# ADIS_Teensy_Arduino_Breakout_RevA.net
KiCad netlist of a schematic drawn in EAGLE
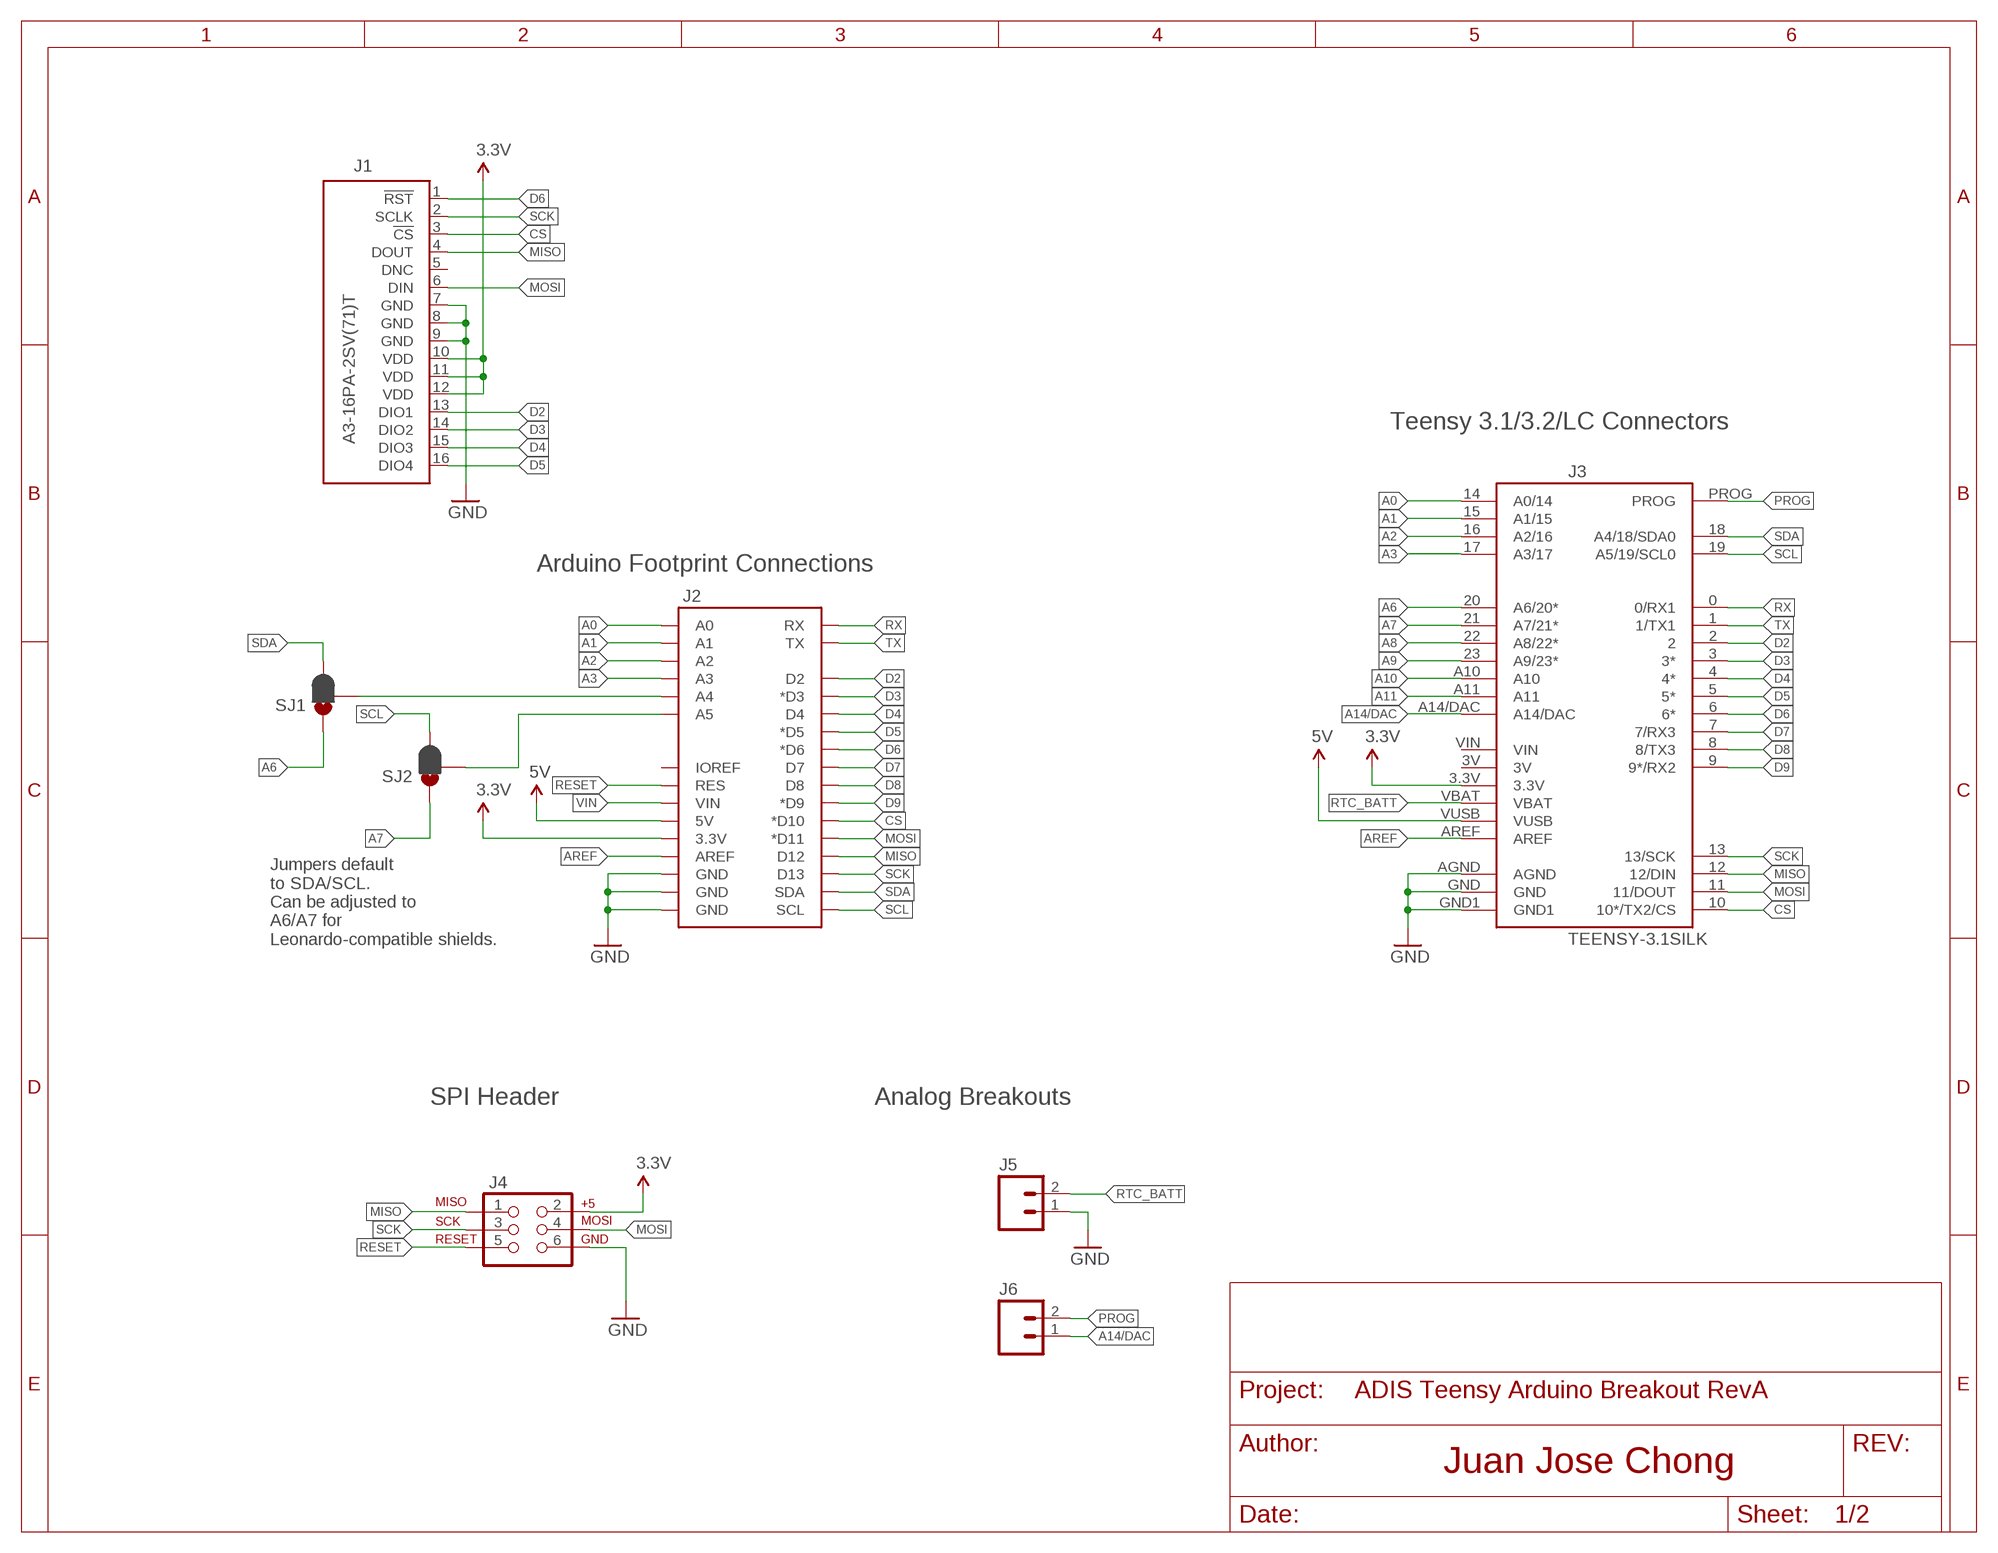
[diagram p0: schematic, sheet 1]
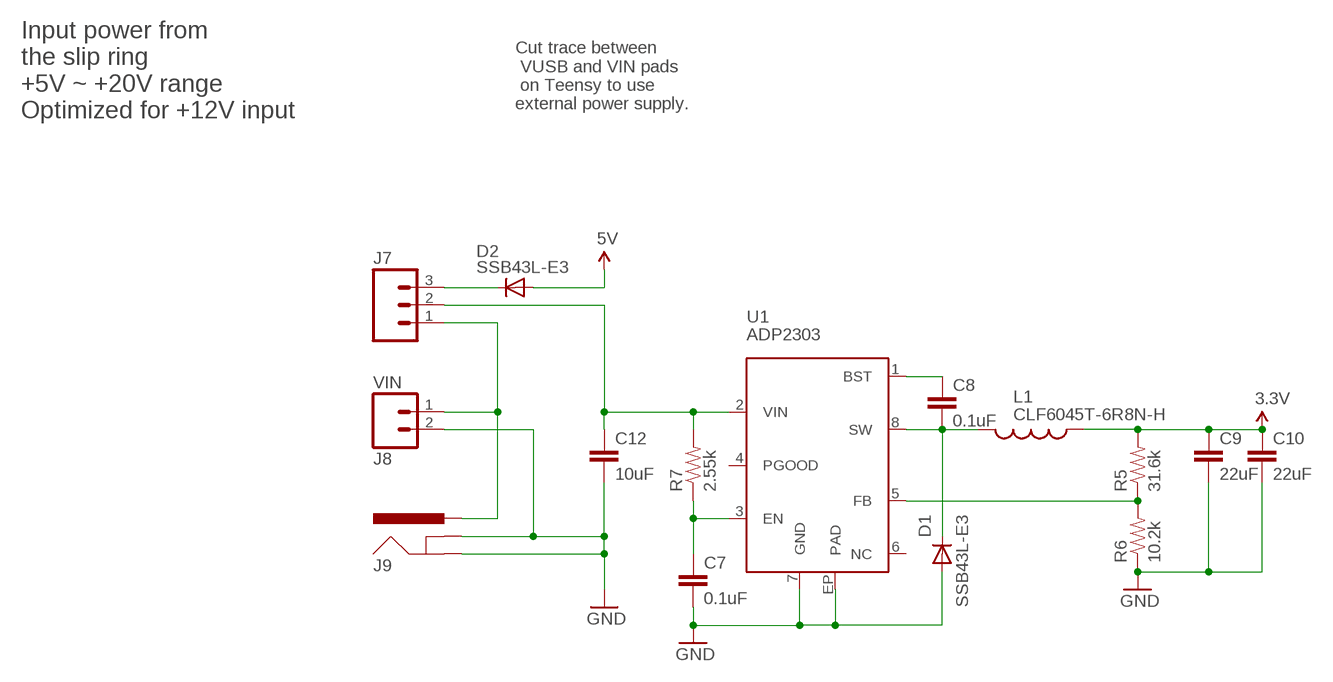
[diagram p1: schematic, sheet 2]

(export (version "E")
  (design (tool "Eeschema 10.0.6"))
  (components
    (comp (ref "C7")
      (value "0.1uF")
      (footprint "eagle-import:0603-CAP")
      (fields (field (name "PARTNO") "CL10B104KB8NNNC"))
      (libsource (lib "eagle-import") (part "CAP0603-CAP"))
    )
    (comp (ref "C8")
      (value "0.1uF")
      (footprint "eagle-import:0603-CAP")
      (fields (field (name "PARTNO") "CL10B104KB8NNNC"))
      (libsource (lib "eagle-import") (part "CAP0603-CAP"))
    )
    (comp (ref "C9")
      (value "22uF")
      (footprint "eagle-import:1210")
      (fields (field (name "PARTNO") "TLJA476M010R0600"))
      (libsource (lib "eagle-import") (part "CAP1210"))
    )
    (comp (ref "C10")
      (value "22uF")
      (footprint "eagle-import:1210")
      (fields (field (name "PARTNO") "TLJA476M010R0600"))
      (libsource (lib "eagle-import") (part "CAP1210"))
    )
    (comp (ref "C12")
      (value "10uF")
      (footprint "eagle-import:1206")
      (fields (field (name "PARTNO") "TLJA476M010R0600"))
      (libsource (lib "eagle-import") (part "CAP1206"))
    )
    (comp (ref "D1")
      (value "SSB43L-E3")
      (footprint "eagle-import:DO214AA")
      (fields (field (name "PARTNO") "SSB43L-E3/52T"))
      (libsource (lib "eagle-import") (part "DIODE-DO214AA"))
    )
    (comp (ref "D2")
      (value "SSB43L-E3")
      (footprint "eagle-import:DO214AA")
      (fields (field (name "PARTNO") "SSB43L-E3/52T"))
      (libsource (lib "eagle-import") (part "DIODE-DO214AA"))
    )
    (comp (ref "J7")
      (value "M03PTH")
      (footprint "eagle-import:1X03")
      (libsource (lib "eagle-import") (part "M03PTH"))
    )
    (comp (ref "J8")
      (value "VIN")
      (footprint "eagle-import:SCREWTERMINAL-3.5MM-2")
      (fields (field (name "PARTNO") "20020327-C021B01LF"))
      (libsource (lib "eagle-import") (part "M023.5MM"))
    )
    (comp (ref "J9")
      (value "POWER_JACKPTH_LOCK")
      (footprint "eagle-import:POWER_JACK_PTH_LOCK")
      (libsource (lib "eagle-import") (part "POWER_JACKPTH_LOCK"))
    )
    (comp (ref "L1")
      (value "CLF6045T-6R8N-H")
      (footprint "eagle-import:CLF6045-H")
      (libsource (lib "eagle-import") (part "CLF6045T-6R8N-H"))
    )
    (comp (ref "R5")
      (value "31.6k")
      (footprint "eagle-import:0603-RES")
      (fields (field (name "PARTNO") "ERJ-3EKF3162V"))
      (libsource (lib "eagle-import") (part "RESISTOR0603-RES"))
    )
    (comp (ref "R6")
      (value "10.2k")
      (footprint "eagle-import:0603-RES")
      (fields (field (name "PARTNO") "ERJ-3EKF1022V"))
      (libsource (lib "eagle-import") (part "RESISTOR0603-RES"))
    )
    (comp (ref "R7")
      (value "2.55k")
      (footprint "eagle-import:0603-RES")
      (fields (field (name "PARTNO") "ERJ-3EKF2551V"))
      (libsource (lib "eagle-import") (part "RESISTOR0603-RES"))
    )
    (comp (ref "U1")
      (value "ADP2303")
      (footprint "eagle-import:SOIC-8-PAD")
      (fields (field (name "PARTNO") "ADP2303ARDZ"))
      (libsource (lib "eagle-import") (part "ADP2303"))
    )
    (comp (ref "J1")
      (value "A3-16PA-2SV(71)T")
      (footprint "eagle-import:A3-16PA-2SV(71)-TOP")
      (libsource (lib "eagle-import") (part "A3-16PA-2SV(71)T"))
    )
    (comp (ref "J2")
      (value "ARDUINO_R3_SHIELDUNO_R3_SHIELD_HOLES")
      (footprint "eagle-import:UNO_R3_SHIELD_HOLES")
      (libsource (lib "eagle-import") (part "ARDUINO_R3_SHIELDUNO_R3_SHIELD_HOLES"))
    )
    (comp (ref "J3")
      (value "TEENSY-3.1SILK")
      (footprint "eagle-import:TEENSY-3.1")
      (libsource (lib "eagle-import") (part "TEENSY-3.1SILK"))
    )
    (comp (ref "J4")
      (value "AVR_SPI_PRG_6PTH")
      (footprint "eagle-import:2X3")
      (libsource (lib "eagle-import") (part "AVR_SPI_PRG_6PTH"))
    )
    (comp (ref "J5")
      (value "M02PTH")
      (footprint "eagle-import:1X02")
      (libsource (lib "eagle-import") (part "M02PTH"))
    )
    (comp (ref "J6")
      (value "M02PTH")
      (footprint "eagle-import:1X02")
      (libsource (lib "eagle-import") (part "M02PTH"))
    )
    (comp (ref "SJ1")
      (value "JUMPER-PAD-3-2OF3_NC_BY_PASTE")
      (footprint "eagle-import:PAD-JUMPER-3-2OF3_NC_BY_PASTE_YES_SILK_FULL_BOX")
      (libsource (lib "eagle-import") (part "JUMPER-PAD-3-2OF3_NC_BY_PASTE"))
    )
    (comp (ref "SJ2")
      (value "JUMPER-PAD-3-2OF3_NC_BY_PASTE")
      (footprint "eagle-import:PAD-JUMPER-3-2OF3_NC_BY_PASTE_YES_SILK_FULL_BOX")
      (libsource (lib "eagle-import") (part "JUMPER-PAD-3-2OF3_NC_BY_PASTE"))
    )
  )
  (nets
    (net (code "1") (name "3.3V") (class "Default")
      (node (ref "C10") (pin "1") (pinfunction "1_1") (pintype "passive"))
      (node (ref "C9") (pin "1") (pinfunction "1_1") (pintype "passive"))
      (node (ref "J1") (pin "10") (pinfunction "VDD_10") (pintype "bidirectional"))
      (node (ref "J1") (pin "11") (pinfunction "VDD_11") (pintype "bidirectional"))
      (node (ref "J1") (pin "12") (pinfunction "VDD_12") (pintype "bidirectional"))
      (node (ref "J2") (pin "3.3V") (pinfunction "3.3V_3.3V") (pintype "bidirectional"))
      (node (ref "J3") (pin "3.3V") (pinfunction "3.3V_3.3V") (pintype "bidirectional"))
      (node (ref "J4") (pin "2") (pinfunction "2_2") (pintype "passive"))
      (node (ref "L1") (pin "P$1") (pinfunction "1_P$1") (pintype "passive"))
      (node (ref "R5") (pin "2") (pinfunction "2_2") (pintype "passive"))
    )
    (net (code "2") (name "5V") (class "Default")
      (node (ref "D2") (pin "A") (pinfunction "A_A") (pintype "passive"))
      (node (ref "J2") (pin "5V") (pinfunction "5V_5V") (pintype "bidirectional"))
      (node (ref "J3") (pin "VUSB") (pinfunction "VUSB_VUSB") (pintype "bidirectional"))
    )
    (net (code "3") (name "A0") (class "Default")
      (node (ref "J2") (pin "A0") (pinfunction "A0_A0") (pintype "bidirectional"))
      (node (ref "J3") (pin "14") (pinfunction "A0/14_14") (pintype "bidirectional"))
    )
    (net (code "4") (name "A1") (class "Default")
      (node (ref "J2") (pin "A1") (pinfunction "A1_A1") (pintype "bidirectional"))
      (node (ref "J3") (pin "15") (pinfunction "A1/15_15") (pintype "bidirectional"))
    )
    (net (code "5") (name "A2") (class "Default")
      (node (ref "J2") (pin "A2") (pinfunction "A2_A2") (pintype "bidirectional"))
      (node (ref "J3") (pin "16") (pinfunction "A2/16_16") (pintype "bidirectional"))
    )
    (net (code "6") (name "A3") (class "Default")
      (node (ref "J2") (pin "A3") (pinfunction "A3_A3") (pintype "bidirectional"))
      (node (ref "J3") (pin "17") (pinfunction "A3/17_17") (pintype "bidirectional"))
    )
    (net (code "7") (name "A6") (class "Default")
      (node (ref "J3") (pin "20") (pinfunction "A6/20*_20") (pintype "bidirectional"))
      (node (ref "SJ1") (pin "1") (pinfunction "1_1") (pintype "passive"))
    )
    (net (code "8") (name "A7") (class "Default")
      (node (ref "J3") (pin "21") (pinfunction "A7/21*_21") (pintype "bidirectional"))
      (node (ref "SJ2") (pin "1") (pinfunction "1_1") (pintype "passive"))
    )
    (net (code "9") (name "A8") (class "Default")
      (node (ref "J3") (pin "22") (pinfunction "A8/22*_22") (pintype "bidirectional"))
    )
    (net (code "10") (name "A9") (class "Default")
      (node (ref "J3") (pin "23") (pinfunction "A9/23*_23") (pintype "bidirectional"))
    )
    (net (code "11") (name "A10") (class "Default")
      (node (ref "J3") (pin "A10") (pinfunction "A10_A10") (pintype "bidirectional"))
    )
    (net (code "12") (name "A11") (class "Default")
      (node (ref "J3") (pin "A11") (pinfunction "A11_A11") (pintype "bidirectional"))
    )
    (net (code "13") (name "A14{slash}DAC") (class "Default")
      (node (ref "J3") (pin "A14/DAC") (pinfunction "A14/DAC_A14/DAC") (pintype "bidirectional"))
      (node (ref "J6") (pin "1") (pinfunction "1_1") (pintype "passive"))
    )
    (net (code "14") (name "AREF") (class "Default")
      (node (ref "J2") (pin "AREF") (pinfunction "AREF_AREF") (pintype "bidirectional"))
      (node (ref "J3") (pin "AREF") (pinfunction "AREF_AREF") (pintype "bidirectional"))
    )
    (net (code "15") (name "CS") (class "Default")
      (node (ref "J1") (pin "3") (pinfunction "~{CS}_3") (pintype "bidirectional"))
      (node (ref "J2") (pin "D10") (pinfunction "*D10_D10") (pintype "bidirectional"))
      (node (ref "J3") (pin "10") (pinfunction "10*/TX2/CS_10") (pintype "bidirectional"))
    )
    (net (code "16") (name "D2") (class "Default")
      (node (ref "J1") (pin "13") (pinfunction "DIO1_13") (pintype "bidirectional"))
      (node (ref "J2") (pin "D2") (pinfunction "D2_D2") (pintype "bidirectional"))
      (node (ref "J3") (pin "2") (pinfunction "2_2") (pintype "bidirectional"))
    )
    (net (code "17") (name "D3") (class "Default")
      (node (ref "J1") (pin "14") (pinfunction "DIO2_14") (pintype "bidirectional"))
      (node (ref "J2") (pin "D3") (pinfunction "*D3_D3") (pintype "bidirectional"))
      (node (ref "J3") (pin "3") (pinfunction "3*_3") (pintype "bidirectional"))
    )
    (net (code "18") (name "D4") (class "Default")
      (node (ref "J1") (pin "15") (pinfunction "DIO3_15") (pintype "bidirectional"))
      (node (ref "J2") (pin "D4") (pinfunction "D4_D4") (pintype "bidirectional"))
      (node (ref "J3") (pin "4") (pinfunction "4*_4") (pintype "bidirectional"))
    )
    (net (code "19") (name "D5") (class "Default")
      (node (ref "J1") (pin "16") (pinfunction "DIO4_16") (pintype "bidirectional"))
      (node (ref "J2") (pin "D5") (pinfunction "*D5_D5") (pintype "bidirectional"))
      (node (ref "J3") (pin "5") (pinfunction "5*_5") (pintype "bidirectional"))
    )
    (net (code "20") (name "D6") (class "Default")
      (node (ref "J1") (pin "1") (pinfunction "~{RST}_1") (pintype "bidirectional"))
      (node (ref "J2") (pin "D6") (pinfunction "*D6_D6") (pintype "bidirectional"))
      (node (ref "J3") (pin "6") (pinfunction "6*_6") (pintype "bidirectional"))
    )
    (net (code "21") (name "D7") (class "Default")
      (node (ref "J2") (pin "D7") (pinfunction "D7_D7") (pintype "bidirectional"))
      (node (ref "J3") (pin "7") (pinfunction "7/RX3_7") (pintype "bidirectional"))
    )
    (net (code "22") (name "D8") (class "Default")
      (node (ref "J2") (pin "D8") (pinfunction "D8_D8") (pintype "bidirectional"))
      (node (ref "J3") (pin "8") (pinfunction "8/TX3_8") (pintype "bidirectional"))
    )
    (net (code "23") (name "D9") (class "Default")
      (node (ref "J2") (pin "D9") (pinfunction "*D9_D9") (pintype "bidirectional"))
      (node (ref "J3") (pin "9") (pinfunction "9*/RX2_9") (pintype "bidirectional"))
    )
    (net (code "24") (name "GND") (class "Default")
      (node (ref "C10") (pin "2") (pinfunction "2_2") (pintype "passive"))
      (node (ref "C12") (pin "2") (pinfunction "2_2") (pintype "passive"))
      (node (ref "C7") (pin "2") (pinfunction "2_2") (pintype "passive"))
      (node (ref "C9") (pin "2") (pinfunction "2_2") (pintype "passive"))
      (node (ref "D1") (pin "A") (pinfunction "A_A") (pintype "passive"))
      (node (ref "J1") (pin "7") (pinfunction "GND_7") (pintype "bidirectional"))
      (node (ref "J1") (pin "8") (pinfunction "GND_8") (pintype "bidirectional"))
      (node (ref "J1") (pin "9") (pinfunction "GND_9") (pintype "bidirectional"))
      (node (ref "J2") (pin "GND@0") (pinfunction "GND_GND@0") (pintype "bidirectional"))
      (node (ref "J2") (pin "GND@1") (pinfunction "GND_GND@1") (pintype "bidirectional"))
      (node (ref "J2") (pin "GND@2") (pinfunction "GND_GND@2") (pintype "bidirectional"))
      (node (ref "J3") (pin "AGND") (pinfunction "AGND_AGND") (pintype "bidirectional"))
      (node (ref "J3") (pin "GND") (pinfunction "GND_GND") (pintype "bidirectional"))
      (node (ref "J3") (pin "GND1") (pinfunction "GND1_GND1") (pintype "bidirectional"))
      (node (ref "J4") (pin "6") (pinfunction "6_6") (pintype "passive"))
      (node (ref "J5") (pin "1") (pinfunction "1_1") (pintype "passive"))
      (node (ref "J8") (pin "2") (pinfunction "2_2") (pintype "passive"))
      (node (ref "J9") (pin "GND") (pinfunction "GND_GND") (pintype "bidirectional"))
      (node (ref "J9") (pin "GNDBREAK") (pinfunction "GNDBREAK_GNDBREAK") (pintype "bidirectional"))
      (node (ref "R6") (pin "1") (pinfunction "1_1") (pintype "passive"))
      (node (ref "U1") (pin "7") (pinfunction "GND_7") (pintype "bidirectional"))
      (node (ref "U1") (pin "EP") (pinfunction "PAD_EP") (pintype "bidirectional"))
    )
    (net (code "25") (name "MISO") (class "Default")
      (node (ref "J1") (pin "4") (pinfunction "DOUT_4") (pintype "bidirectional"))
      (node (ref "J2") (pin "D12") (pinfunction "D12_D12") (pintype "bidirectional"))
      (node (ref "J3") (pin "12") (pinfunction "12/DIN_12") (pintype "bidirectional"))
      (node (ref "J4") (pin "1") (pinfunction "1_1") (pintype "passive"))
    )
    (net (code "26") (name "MOSI") (class "Default")
      (node (ref "J1") (pin "6") (pinfunction "DIN_6") (pintype "bidirectional"))
      (node (ref "J2") (pin "D11") (pinfunction "*D11_D11") (pintype "bidirectional"))
      (node (ref "J3") (pin "11") (pinfunction "11/DOUT_11") (pintype "bidirectional"))
      (node (ref "J4") (pin "4") (pinfunction "4_4") (pintype "passive"))
    )
    (net (code "27") (name "Net-(D2-PadC)") (class "Default")
      (node (ref "D2") (pin "C") (pinfunction "C_C") (pintype "passive"))
      (node (ref "J7") (pin "3") (pinfunction "3_3") (pintype "passive"))
    )
    (net (code "28") (name "Net-(J2-PadA4)") (class "Default")
      (node (ref "J2") (pin "A4") (pinfunction "A4_A4") (pintype "bidirectional"))
      (node (ref "SJ1") (pin "2") (pinfunction "2_2") (pintype "passive"))
    )
    (net (code "29") (name "Net-(J2-PadA5)") (class "Default")
      (node (ref "J2") (pin "A5") (pinfunction "A5_A5") (pintype "bidirectional"))
      (node (ref "SJ2") (pin "2") (pinfunction "2_2") (pintype "passive"))
    )
    (net (code "30") (name "Net-(J7-Pad1)") (class "Default")
      (node (ref "J7") (pin "1") (pinfunction "1_1") (pintype "passive"))
      (node (ref "J8") (pin "1") (pinfunction "1_1") (pintype "passive"))
      (node (ref "J9") (pin "PWR") (pinfunction "PWR_PWR") (pintype "bidirectional"))
    )
    (net (code "31") (name "Net-(L1-2)") (class "Default")
      (node (ref "C8") (pin "2") (pinfunction "2_2") (pintype "passive"))
      (node (ref "D1") (pin "C") (pinfunction "C_C") (pintype "passive"))
      (node (ref "L1") (pin "P$2") (pinfunction "2_P$2") (pintype "passive"))
      (node (ref "U1") (pin "8") (pinfunction "SW_8") (pintype "bidirectional"))
    )
    (net (code "32") (name "Net-(U1-BST)") (class "Default")
      (node (ref "C8") (pin "1") (pinfunction "1_1") (pintype "passive"))
      (node (ref "U1") (pin "1") (pinfunction "BST_1") (pintype "bidirectional"))
    )
    (net (code "33") (name "Net-(U1-EN)") (class "Default")
      (node (ref "C7") (pin "1") (pinfunction "1_1") (pintype "passive"))
      (node (ref "R7") (pin "1") (pinfunction "1_1") (pintype "passive"))
      (node (ref "U1") (pin "3") (pinfunction "EN_3") (pintype "bidirectional"))
    )
    (net (code "34") (name "Net-(U1-FB)") (class "Default")
      (node (ref "R5") (pin "1") (pinfunction "1_1") (pintype "passive"))
      (node (ref "R6") (pin "2") (pinfunction "2_2") (pintype "passive"))
      (node (ref "U1") (pin "5") (pinfunction "FB_5") (pintype "bidirectional"))
    )
    (net (code "35") (name "Net-(U1-VIN)") (class "Default")
      (node (ref "C12") (pin "1") (pinfunction "1_1") (pintype "passive"))
      (node (ref "J7") (pin "2") (pinfunction "2_2") (pintype "passive"))
      (node (ref "R7") (pin "2") (pinfunction "2_2") (pintype "passive"))
      (node (ref "U1") (pin "2") (pinfunction "VIN_2") (pintype "bidirectional"))
    )
    (net (code "36") (name "PROG") (class "Default")
      (node (ref "J3") (pin "PROG") (pinfunction "PROG_PROG") (pintype "bidirectional"))
      (node (ref "J6") (pin "2") (pinfunction "2_2") (pintype "passive"))
    )
    (net (code "37") (name "RESET") (class "Default")
      (node (ref "J2") (pin "RES") (pinfunction "RES_RES") (pintype "bidirectional"))
      (node (ref "J4") (pin "5") (pinfunction "5_5") (pintype "passive"))
    )
    (net (code "38") (name "RTC_BATT") (class "Default")
      (node (ref "J3") (pin "VBAT") (pinfunction "VBAT_VBAT") (pintype "bidirectional"))
      (node (ref "J5") (pin "2") (pinfunction "2_2") (pintype "passive"))
    )
    (net (code "39") (name "RX") (class "Default")
      (node (ref "J2") (pin "RX") (pinfunction "RX_RX") (pintype "bidirectional"))
      (node (ref "J3") (pin "0") (pinfunction "0/RX1_0") (pintype "bidirectional"))
    )
    (net (code "40") (name "SCK") (class "Default")
      (node (ref "J1") (pin "2") (pinfunction "SCLK_2") (pintype "bidirectional"))
      (node (ref "J2") (pin "D13") (pinfunction "D13_D13") (pintype "bidirectional"))
      (node (ref "J3") (pin "13") (pinfunction "13/SCK_13") (pintype "bidirectional"))
      (node (ref "J4") (pin "3") (pinfunction "3_3") (pintype "passive"))
    )
    (net (code "41") (name "SCL") (class "Default")
      (node (ref "J2") (pin "SCL") (pinfunction "SCL_SCL") (pintype "bidirectional"))
      (node (ref "J3") (pin "19") (pinfunction "A5/19/SCL0_19") (pintype "bidirectional"))
      (node (ref "SJ2") (pin "3") (pinfunction "3_3") (pintype "passive"))
    )
    (net (code "42") (name "SDA") (class "Default")
      (node (ref "J2") (pin "SDA") (pinfunction "SDA_SDA") (pintype "bidirectional"))
      (node (ref "J3") (pin "18") (pinfunction "A4/18/SDA0_18") (pintype "bidirectional"))
      (node (ref "SJ1") (pin "3") (pinfunction "3_3") (pintype "passive"))
    )
    (net (code "43") (name "TX") (class "Default")
      (node (ref "J2") (pin "TX") (pinfunction "TX_TX") (pintype "bidirectional"))
      (node (ref "J3") (pin "1") (pinfunction "1/TX1_1") (pintype "bidirectional"))
    )
    (net (code "44") (name "VIN") (class "Default")
      (node (ref "J2") (pin "VIN") (pinfunction "VIN_VIN") (pintype "bidirectional"))
    )
    (net (code "45") (name "unconnected-(J1-DNC-Pad5)") (class "Default")
      (node (ref "J1") (pin "5") (pinfunction "DNC_5") (pintype "bidirectional"))
    )
    (net (code "46") (name "unconnected-(J2-PadIOREF)") (class "Default")
      (node (ref "J2") (pin "IOREF") (pinfunction "IOREF_IOREF") (pintype "bidirectional"))
    )
    (net (code "47") (name "unconnected-(J3-Pad3V)") (class "Default")
      (node (ref "J3") (pin "3V") (pinfunction "3V_3V") (pintype "bidirectional"))
    )
    (net (code "48") (name "unconnected-(J3-PadVIN)") (class "Default")
      (node (ref "J3") (pin "VIN") (pinfunction "VIN_VIN") (pintype "bidirectional"))
    )
    (net (code "49") (name "unconnected-(U1-NC-Pad6)") (class "Default")
      (node (ref "U1") (pin "6") (pinfunction "NC_6") (pintype "bidirectional"))
    )
    (net (code "50") (name "unconnected-(U1-PGOOD-Pad4)") (class "Default")
      (node (ref "U1") (pin "4") (pinfunction "PGOOD_4") (pintype "bidirectional"))
    )
  )
)
